# encoder.net
KiCad netlist of a schematic drawn in EAGLE
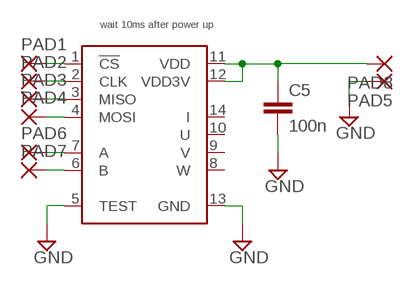
[diagram p0: schematic, sheet 1]

(export (version "E")
  (design (tool "Eeschema 10.0.6"))
  (components
    (comp (ref "C5")
      (value "100n")
      (footprint "eagle-import:C0603")
      (libsource (lib "eagle-import") (part "C-EUC0603"))
    )
    (comp (ref "PAD1")
      (value "SMD2")
      (footprint "eagle-import:SMD1,27-2,54")
      (libsource (lib "eagle-import") (part "SMD2"))
    )
    (comp (ref "PAD2")
      (value "SMD2")
      (footprint "eagle-import:SMD1,27-2,54")
      (libsource (lib "eagle-import") (part "SMD2"))
    )
    (comp (ref "PAD3")
      (value "SMD2")
      (footprint "eagle-import:SMD1,27-2,54")
      (libsource (lib "eagle-import") (part "SMD2"))
    )
    (comp (ref "PAD4")
      (value "SMD2")
      (footprint "eagle-import:SMD1,27-2,54")
      (libsource (lib "eagle-import") (part "SMD2"))
    )
    (comp (ref "PAD5")
      (value "SMD2")
      (footprint "eagle-import:SMD1,27-2,54")
      (libsource (lib "eagle-import") (part "SMD2"))
    )
    (comp (ref "PAD6")
      (value "SMD2")
      (footprint "eagle-import:SMD1,27-2,54")
      (libsource (lib "eagle-import") (part "SMD2"))
    )
    (comp (ref "PAD7")
      (value "SMD2")
      (footprint "eagle-import:SMD1,27-2,54")
      (libsource (lib "eagle-import") (part "SMD2"))
    )
    (comp (ref "PAD8")
      (value "SMD2")
      (footprint "eagle-import:SMD1,27-2,54")
      (libsource (lib "eagle-import") (part "SMD2"))
    )
    (comp (ref "U$1")
      (value "AS5147P")
      (footprint "eagle-import:TSSOP-14")
      (libsource (lib "eagle-import") (part "AS5147P"))
    )
  )
  (nets
    (net (code "1") (name "GND") (class "Default")
      (node (ref "C5") (pin "2") (pinfunction "2_2") (pintype "passive"))
      (node (ref "PAD5") (pin "1") (pinfunction "P_1") (pintype "passive"))
      (node (ref "U$1") (pin "13") (pinfunction "GND_13") (pintype "bidirectional"))
      (node (ref "U$1") (pin "5") (pinfunction "TEST_5") (pintype "bidirectional"))
    )
    (net (code "2") (name "Net-(PAD1-P)") (class "Default")
      (node (ref "PAD1") (pin "1") (pinfunction "P_1") (pintype "passive"))
      (node (ref "U$1") (pin "1") (pinfunction "~{CS}_1") (pintype "bidirectional"))
    )
    (net (code "3") (name "Net-(PAD2-P)") (class "Default")
      (node (ref "PAD2") (pin "1") (pinfunction "P_1") (pintype "passive"))
      (node (ref "U$1") (pin "2") (pinfunction "CLK_2") (pintype "bidirectional"))
    )
    (net (code "4") (name "Net-(PAD3-P)") (class "Default")
      (node (ref "PAD3") (pin "1") (pinfunction "P_1") (pintype "passive"))
      (node (ref "U$1") (pin "3") (pinfunction "MISO_3") (pintype "bidirectional"))
    )
    (net (code "5") (name "Net-(PAD4-P)") (class "Default")
      (node (ref "PAD4") (pin "1") (pinfunction "P_1") (pintype "passive"))
      (node (ref "U$1") (pin "4") (pinfunction "MOSI_4") (pintype "bidirectional"))
    )
    (net (code "6") (name "Net-(PAD6-P)") (class "Default")
      (node (ref "PAD6") (pin "1") (pinfunction "P_1") (pintype "passive"))
      (node (ref "U$1") (pin "7") (pinfunction "A_7") (pintype "bidirectional"))
    )
    (net (code "7") (name "Net-(PAD7-P)") (class "Default")
      (node (ref "PAD7") (pin "1") (pinfunction "P_1") (pintype "passive"))
      (node (ref "U$1") (pin "6") (pinfunction "B_6") (pintype "bidirectional"))
    )
    (net (code "8") (name "Net-(PAD8-P)") (class "Default")
      (node (ref "C5") (pin "1") (pinfunction "1_1") (pintype "passive"))
      (node (ref "PAD8") (pin "1") (pinfunction "P_1") (pintype "passive"))
      (node (ref "U$1") (pin "11") (pinfunction "VDD_11") (pintype "bidirectional"))
      (node (ref "U$1") (pin "12") (pinfunction "VDD3V_12") (pintype "bidirectional"))
    )
    (net (code "9") (name "unconnected-(U$1-I-Pad14)") (class "Default")
      (node (ref "U$1") (pin "14") (pinfunction "I_14") (pintype "bidirectional"))
    )
    (net (code "10") (name "unconnected-(U$1-U-Pad10)") (class "Default")
      (node (ref "U$1") (pin "10") (pinfunction "U_10") (pintype "bidirectional"))
    )
    (net (code "11") (name "unconnected-(U$1-V-Pad9)") (class "Default")
      (node (ref "U$1") (pin "9") (pinfunction "V_9") (pintype "bidirectional"))
    )
    (net (code "12") (name "unconnected-(U$1-W-Pad8)") (class "Default")
      (node (ref "U$1") (pin "8") (pinfunction "W_8") (pintype "bidirectional"))
    )
  )
)
